# DRAM_BANK1.net
KiCad netlist of a schematic drawn in Altium Designer
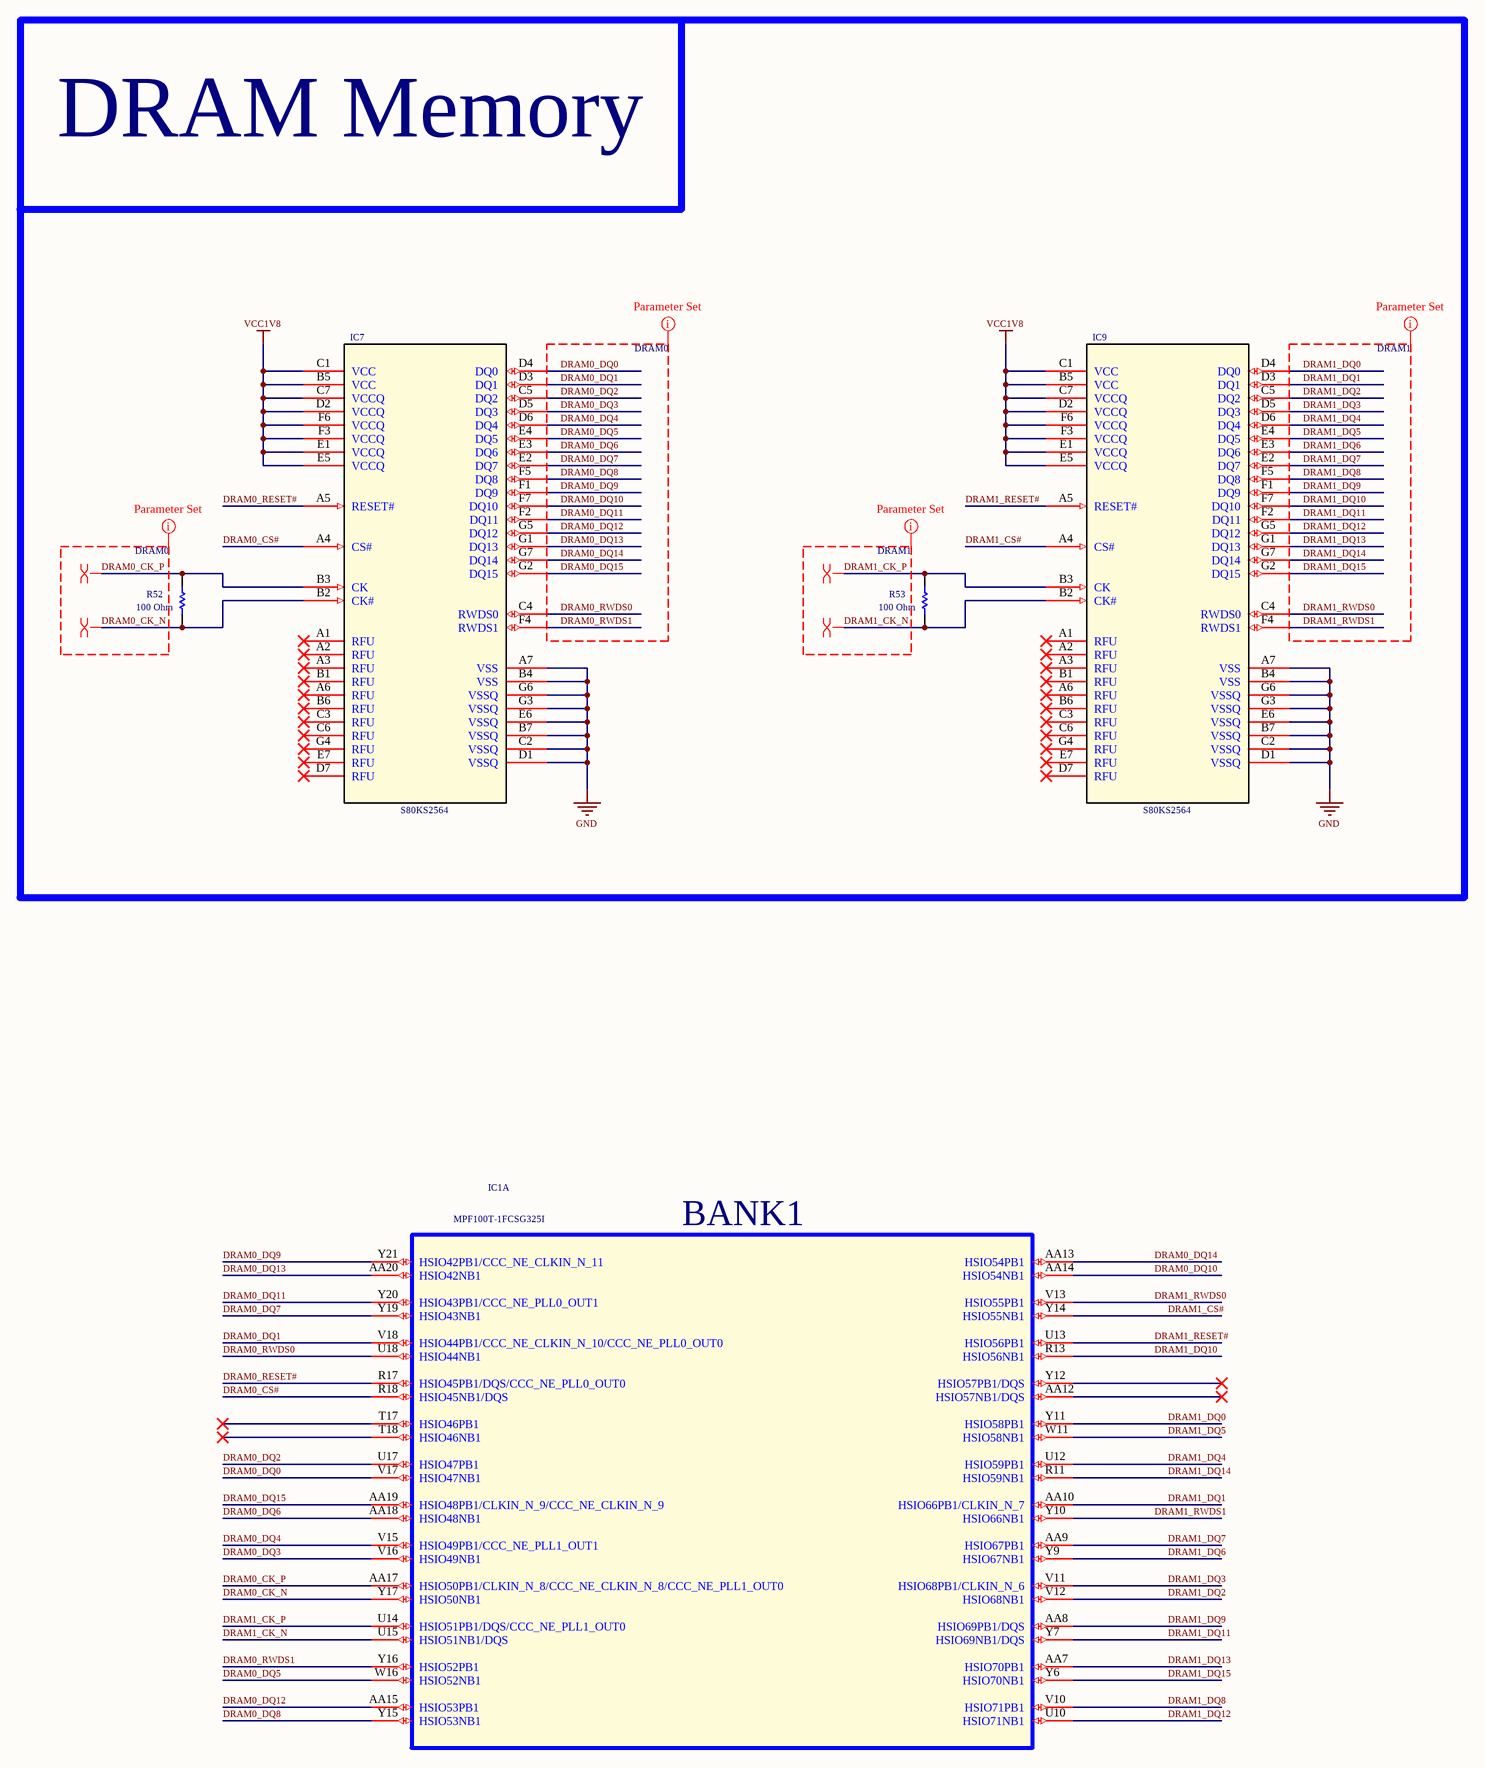
[diagram p0: DRAM+BANK1.SchDoc]

(export (version "E")
  (design (tool "Eeschema 10.0.6"))
  (components
    (comp (ref "IC1")
      (value "MPF100T-1FCSG325I")
      (footprint "PCB_Display_Doru:MPF100T-1FCSG325I")
      (fields (field (name "PART_NUMBER") "J00001"))
      (libsource (lib "PCB_Display_Doru") (part "MPF100T-1FCSG325I"))
    )
    (comp (ref "IC7")
      (value "S80KS2564")
      (footprint "PCB_Display_Doru:S80KS2564")
      (description "Jumper")
      (fields (field (name "PART_NUMBER") "J00001"))
      (libsource (lib "PCB_Display_Doru") (part "S80KS2564"))
    )
    (comp (ref "IC9")
      (value "S80KS2564")
      (footprint "PCB_Display_Doru:S80KS2564")
      (description "Jumper")
      (fields (field (name "PART_NUMBER") "J00001"))
      (libsource (lib "PCB_Display_Doru") (part "S80KS2564"))
    )
    (comp (ref "R52")
      (value "100 Ohm")
      (footprint "RESC1608X55X30LL15T15")
      (fields
        (field (name "MANUFACTURER") "Panasonic")
        (field (name "PART NUMBER") "ERJ-3EKF1000V")
        (field (name "MANUFACTURER PART NUMBER") "ERJ3EKF1000V")
      )
      (libsource (lib "PCB_Display_Doru") (part "CMP-2000-00179-1"))
    )
    (comp (ref "R53")
      (value "100 Ohm")
      (footprint "RESC1608X55X30LL15T15")
      (fields
        (field (name "MANUFACTURER") "Panasonic")
        (field (name "PART NUMBER") "ERJ-3EKF1000V")
        (field (name "MANUFACTURER PART NUMBER") "ERJ3EKF1000V")
      )
      (libsource (lib "PCB_Display_Doru") (part "CMP-2000-00179-1"))
    )
  )
  (nets
    (net (code "1") (name "/DRAM0_CK_N") (class "Default")
      (node (ref "IC1") (pin "Y17") (pinfunction "HSIO50NB1_Y17") (pintype "bidirectional"))
      (node (ref "IC7") (pin "B2") (pinfunction "CK#_B2") (pintype "input"))
      (node (ref "R52") (pin "1") (pinfunction "1_1") (pintype "passive"))
    )
    (net (code "2") (name "/DRAM0_CK_P") (class "Default")
      (node (ref "IC1") (pin "AA17") (pinfunction "HSIO50PB1/CLKIN_N_8/CCC_NE_CLKIN_N_8/CCC_NE_PLL1_OUT0_AA17") (pintype "bidirectional"))
      (node (ref "IC7") (pin "B3") (pinfunction "CK_B3") (pintype "input"))
      (node (ref "R52") (pin "2") (pinfunction "2_2") (pintype "passive"))
    )
    (net (code "3") (name "/DRAM0_CS#") (class "Default")
      (node (ref "IC1") (pin "R18") (pinfunction "HSIO45NB1/DQS_R18") (pintype "bidirectional"))
      (node (ref "IC7") (pin "A4") (pinfunction "CS#_A4") (pintype "input"))
    )
    (net (code "4") (name "/DRAM0_DQ0") (class "Default")
      (node (ref "IC1") (pin "V17") (pinfunction "HSIO47NB1_V17") (pintype "bidirectional"))
      (node (ref "IC7") (pin "D4") (pinfunction "DQ0_D4") (pintype "bidirectional"))
    )
    (net (code "5") (name "/DRAM0_DQ1") (class "Default")
      (node (ref "IC1") (pin "V18") (pinfunction "HSIO44PB1/CCC_NE_CLKIN_N_10/CCC_NE_PLL0_OUT0_V18") (pintype "bidirectional"))
      (node (ref "IC7") (pin "D3") (pinfunction "DQ1_D3") (pintype "bidirectional"))
    )
    (net (code "6") (name "/DRAM0_DQ2") (class "Default")
      (node (ref "IC1") (pin "U17") (pinfunction "HSIO47PB1_U17") (pintype "bidirectional"))
      (node (ref "IC7") (pin "C5") (pinfunction "DQ2_C5") (pintype "bidirectional"))
    )
    (net (code "7") (name "/DRAM0_DQ3") (class "Default")
      (node (ref "IC1") (pin "V16") (pinfunction "HSIO49NB1_V16") (pintype "bidirectional"))
      (node (ref "IC7") (pin "D5") (pinfunction "DQ3_D5") (pintype "bidirectional"))
    )
    (net (code "8") (name "/DRAM0_DQ4") (class "Default")
      (node (ref "IC1") (pin "V15") (pinfunction "HSIO49PB1/CCC_NE_PLL1_OUT1_V15") (pintype "bidirectional"))
      (node (ref "IC7") (pin "D6") (pinfunction "DQ4_D6") (pintype "bidirectional"))
    )
    (net (code "9") (name "/DRAM0_DQ5") (class "Default")
      (node (ref "IC1") (pin "W16") (pinfunction "HSIO52NB1_W16") (pintype "bidirectional"))
      (node (ref "IC7") (pin "E4") (pinfunction "DQ5_E4") (pintype "bidirectional"))
    )
    (net (code "10") (name "/DRAM0_DQ6") (class "Default")
      (node (ref "IC1") (pin "AA18") (pinfunction "HSIO48NB1_AA18") (pintype "bidirectional"))
      (node (ref "IC7") (pin "E3") (pinfunction "DQ6_E3") (pintype "bidirectional"))
    )
    (net (code "11") (name "/DRAM0_DQ7") (class "Default")
      (node (ref "IC1") (pin "Y19") (pinfunction "HSIO43NB1_Y19") (pintype "bidirectional"))
      (node (ref "IC7") (pin "E2") (pinfunction "DQ7_E2") (pintype "bidirectional"))
    )
    (net (code "12") (name "/DRAM0_DQ8") (class "Default")
      (node (ref "IC1") (pin "Y15") (pinfunction "HSIO53NB1_Y15") (pintype "bidirectional"))
      (node (ref "IC7") (pin "F5") (pinfunction "DQ8_F5") (pintype "bidirectional"))
    )
    (net (code "13") (name "/DRAM0_DQ9") (class "Default")
      (node (ref "IC1") (pin "Y21") (pinfunction "HSIO42PB1/CCC_NE_CLKIN_N_11_Y21") (pintype "bidirectional"))
      (node (ref "IC7") (pin "F1") (pinfunction "DQ9_F1") (pintype "bidirectional"))
    )
    (net (code "14") (name "/DRAM0_DQ10") (class "Default")
      (node (ref "IC1") (pin "AA14") (pinfunction "HSIO54NB1_AA14") (pintype "bidirectional"))
      (node (ref "IC7") (pin "F7") (pinfunction "DQ10_F7") (pintype "bidirectional"))
    )
    (net (code "15") (name "/DRAM0_DQ11") (class "Default")
      (node (ref "IC1") (pin "Y20") (pinfunction "HSIO43PB1/CCC_NE_PLL0_OUT1_Y20") (pintype "bidirectional"))
      (node (ref "IC7") (pin "F2") (pinfunction "DQ11_F2") (pintype "bidirectional"))
    )
    (net (code "16") (name "/DRAM0_DQ12") (class "Default")
      (node (ref "IC1") (pin "AA15") (pinfunction "HSIO53PB1_AA15") (pintype "bidirectional"))
      (node (ref "IC7") (pin "G5") (pinfunction "DQ12_G5") (pintype "bidirectional"))
    )
    (net (code "17") (name "/DRAM0_DQ13") (class "Default")
      (node (ref "IC1") (pin "AA20") (pinfunction "HSIO42NB1_AA20") (pintype "bidirectional"))
      (node (ref "IC7") (pin "G1") (pinfunction "DQ13_G1") (pintype "bidirectional"))
    )
    (net (code "18") (name "/DRAM0_DQ14") (class "Default")
      (node (ref "IC1") (pin "AA13") (pinfunction "HSIO54PB1_AA13") (pintype "bidirectional"))
      (node (ref "IC7") (pin "G7") (pinfunction "DQ14_G7") (pintype "bidirectional"))
    )
    (net (code "19") (name "/DRAM0_DQ15") (class "Default")
      (node (ref "IC1") (pin "AA19") (pinfunction "HSIO48PB1/CLKIN_N_9/CCC_NE_CLKIN_N_9_AA19") (pintype "bidirectional"))
      (node (ref "IC7") (pin "G2") (pinfunction "DQ15_G2") (pintype "bidirectional"))
    )
    (net (code "20") (name "/DRAM0_RESET#") (class "Default")
      (node (ref "IC1") (pin "R17") (pinfunction "HSIO45PB1/DQS/CCC_NE_PLL0_OUT0_R17") (pintype "bidirectional"))
      (node (ref "IC7") (pin "A5") (pinfunction "RESET#_A5") (pintype "input"))
    )
    (net (code "21") (name "/DRAM0_RWDS0") (class "Default")
      (node (ref "IC1") (pin "U18") (pinfunction "HSIO44NB1_U18") (pintype "bidirectional"))
      (node (ref "IC7") (pin "C4") (pinfunction "RWDS0_C4") (pintype "bidirectional"))
    )
    (net (code "22") (name "/DRAM0_RWDS1") (class "Default")
      (node (ref "IC1") (pin "Y16") (pinfunction "HSIO52PB1_Y16") (pintype "bidirectional"))
      (node (ref "IC7") (pin "F4") (pinfunction "RWDS1_F4") (pintype "bidirectional"))
    )
    (net (code "23") (name "/DRAM1_CK_N") (class "Default")
      (node (ref "IC1") (pin "U15") (pinfunction "HSIO51NB1/DQS_U15") (pintype "bidirectional"))
      (node (ref "IC9") (pin "B2") (pinfunction "CK#_B2") (pintype "input"))
      (node (ref "R53") (pin "1") (pinfunction "1_1") (pintype "passive"))
    )
    (net (code "24") (name "/DRAM1_CK_P") (class "Default")
      (node (ref "IC1") (pin "U14") (pinfunction "HSIO51PB1/DQS/CCC_NE_PLL1_OUT0_U14") (pintype "bidirectional"))
      (node (ref "IC9") (pin "B3") (pinfunction "CK_B3") (pintype "input"))
      (node (ref "R53") (pin "2") (pinfunction "2_2") (pintype "passive"))
    )
    (net (code "25") (name "/DRAM1_CS#") (class "Default")
      (node (ref "IC1") (pin "Y14") (pinfunction "HSIO55NB1_Y14") (pintype "bidirectional"))
      (node (ref "IC9") (pin "A4") (pinfunction "CS#_A4") (pintype "input"))
    )
    (net (code "26") (name "/DRAM1_DQ0") (class "Default")
      (node (ref "IC1") (pin "Y11") (pinfunction "HSIO58PB1_Y11") (pintype "bidirectional"))
      (node (ref "IC9") (pin "D4") (pinfunction "DQ0_D4") (pintype "bidirectional"))
    )
    (net (code "27") (name "/DRAM1_DQ1") (class "Default")
      (node (ref "IC1") (pin "AA10") (pinfunction "HSIO66PB1/CLKIN_N_7_AA10") (pintype "bidirectional"))
      (node (ref "IC9") (pin "D3") (pinfunction "DQ1_D3") (pintype "bidirectional"))
    )
    (net (code "28") (name "/DRAM1_DQ2") (class "Default")
      (node (ref "IC1") (pin "V12") (pinfunction "HSIO68NB1_V12") (pintype "bidirectional"))
      (node (ref "IC9") (pin "C5") (pinfunction "DQ2_C5") (pintype "bidirectional"))
    )
    (net (code "29") (name "/DRAM1_DQ3") (class "Default")
      (node (ref "IC1") (pin "V11") (pinfunction "HSIO68PB1/CLKIN_N_6_V11") (pintype "bidirectional"))
      (node (ref "IC9") (pin "D5") (pinfunction "DQ3_D5") (pintype "bidirectional"))
    )
    (net (code "30") (name "/DRAM1_DQ4") (class "Default")
      (node (ref "IC1") (pin "U12") (pinfunction "HSIO59PB1_U12") (pintype "bidirectional"))
      (node (ref "IC9") (pin "D6") (pinfunction "DQ4_D6") (pintype "bidirectional"))
    )
    (net (code "31") (name "/DRAM1_DQ5") (class "Default")
      (node (ref "IC1") (pin "W11") (pinfunction "HSIO58NB1_W11") (pintype "bidirectional"))
      (node (ref "IC9") (pin "E4") (pinfunction "DQ5_E4") (pintype "bidirectional"))
    )
    (net (code "32") (name "/DRAM1_DQ6") (class "Default")
      (node (ref "IC1") (pin "Y9") (pinfunction "HSIO67NB1_Y9") (pintype "bidirectional"))
      (node (ref "IC9") (pin "E3") (pinfunction "DQ6_E3") (pintype "bidirectional"))
    )
    (net (code "33") (name "/DRAM1_DQ7") (class "Default")
      (node (ref "IC1") (pin "AA9") (pinfunction "HSIO67PB1_AA9") (pintype "bidirectional"))
      (node (ref "IC9") (pin "E2") (pinfunction "DQ7_E2") (pintype "bidirectional"))
    )
    (net (code "34") (name "/DRAM1_DQ8") (class "Default")
      (node (ref "IC1") (pin "V10") (pinfunction "HSIO71PB1_V10") (pintype "bidirectional"))
      (node (ref "IC9") (pin "F5") (pinfunction "DQ8_F5") (pintype "bidirectional"))
    )
    (net (code "35") (name "/DRAM1_DQ9") (class "Default")
      (node (ref "IC1") (pin "AA8") (pinfunction "HSIO69PB1/DQS_AA8") (pintype "bidirectional"))
      (node (ref "IC9") (pin "F1") (pinfunction "DQ9_F1") (pintype "bidirectional"))
    )
    (net (code "36") (name "/DRAM1_DQ10") (class "Default")
      (node (ref "IC1") (pin "R13") (pinfunction "HSIO56NB1_R13") (pintype "bidirectional"))
      (node (ref "IC9") (pin "F7") (pinfunction "DQ10_F7") (pintype "bidirectional"))
    )
    (net (code "37") (name "/DRAM1_DQ11") (class "Default")
      (node (ref "IC1") (pin "Y7") (pinfunction "HSIO69NB1/DQS_Y7") (pintype "bidirectional"))
      (node (ref "IC9") (pin "F2") (pinfunction "DQ11_F2") (pintype "bidirectional"))
    )
    (net (code "38") (name "/DRAM1_DQ12") (class "Default")
      (node (ref "IC1") (pin "U10") (pinfunction "HSIO71NB1_U10") (pintype "bidirectional"))
      (node (ref "IC9") (pin "G5") (pinfunction "DQ12_G5") (pintype "bidirectional"))
    )
    (net (code "39") (name "/DRAM1_DQ13") (class "Default")
      (node (ref "IC1") (pin "AA7") (pinfunction "HSIO70PB1_AA7") (pintype "bidirectional"))
      (node (ref "IC9") (pin "G1") (pinfunction "DQ13_G1") (pintype "bidirectional"))
    )
    (net (code "40") (name "/DRAM1_DQ14") (class "Default")
      (node (ref "IC1") (pin "R11") (pinfunction "HSIO59NB1_R11") (pintype "bidirectional"))
      (node (ref "IC9") (pin "G7") (pinfunction "DQ14_G7") (pintype "bidirectional"))
    )
    (net (code "41") (name "/DRAM1_DQ15") (class "Default")
      (node (ref "IC1") (pin "Y6") (pinfunction "HSIO70NB1_Y6") (pintype "bidirectional"))
      (node (ref "IC9") (pin "G2") (pinfunction "DQ15_G2") (pintype "bidirectional"))
    )
    (net (code "42") (name "/DRAM1_RESET#") (class "Default")
      (node (ref "IC1") (pin "U13") (pinfunction "HSIO56PB1_U13") (pintype "bidirectional"))
      (node (ref "IC9") (pin "A5") (pinfunction "RESET#_A5") (pintype "input"))
    )
    (net (code "43") (name "/DRAM1_RWDS0") (class "Default")
      (node (ref "IC1") (pin "V13") (pinfunction "HSIO55PB1_V13") (pintype "bidirectional"))
      (node (ref "IC9") (pin "C4") (pinfunction "RWDS0_C4") (pintype "bidirectional"))
    )
    (net (code "44") (name "/DRAM1_RWDS1") (class "Default")
      (node (ref "IC1") (pin "Y10") (pinfunction "HSIO66NB1_Y10") (pintype "bidirectional"))
      (node (ref "IC9") (pin "F4") (pinfunction "RWDS1_F4") (pintype "bidirectional"))
    )
    (net (code "45") (name "GND") (class "Default")
      (node (ref "IC7") (pin "A7") (pinfunction "VSS_A7") (pintype "power_in"))
      (node (ref "IC7") (pin "B4") (pinfunction "VSS_B4") (pintype "power_in"))
      (node (ref "IC7") (pin "B7") (pinfunction "VSSQ_B7") (pintype "power_in"))
      (node (ref "IC7") (pin "C2") (pinfunction "VSSQ_C2") (pintype "power_in"))
      (node (ref "IC7") (pin "D1") (pinfunction "VSSQ_D1") (pintype "power_in"))
      (node (ref "IC7") (pin "E6") (pinfunction "VSSQ_E6") (pintype "power_in"))
      (node (ref "IC7") (pin "G3") (pinfunction "VSSQ_G3") (pintype "power_in"))
      (node (ref "IC7") (pin "G6") (pinfunction "VSSQ_G6") (pintype "power_in"))
      (node (ref "IC9") (pin "A7") (pinfunction "VSS_A7") (pintype "power_in"))
      (node (ref "IC9") (pin "B4") (pinfunction "VSS_B4") (pintype "power_in"))
      (node (ref "IC9") (pin "B7") (pinfunction "VSSQ_B7") (pintype "power_in"))
      (node (ref "IC9") (pin "C2") (pinfunction "VSSQ_C2") (pintype "power_in"))
      (node (ref "IC9") (pin "D1") (pinfunction "VSSQ_D1") (pintype "power_in"))
      (node (ref "IC9") (pin "E6") (pinfunction "VSSQ_E6") (pintype "power_in"))
      (node (ref "IC9") (pin "G3") (pinfunction "VSSQ_G3") (pintype "power_in"))
      (node (ref "IC9") (pin "G6") (pinfunction "VSSQ_G6") (pintype "power_in"))
    )
    (net (code "46") (name "VCC1V8") (class "Default")
      (node (ref "IC7") (pin "B5") (pinfunction "VCC_B5") (pintype "power_in"))
      (node (ref "IC7") (pin "C1") (pinfunction "VCC_C1") (pintype "power_in"))
      (node (ref "IC7") (pin "C7") (pinfunction "VCCQ_C7") (pintype "power_in"))
      (node (ref "IC7") (pin "D2") (pinfunction "VCCQ_D2") (pintype "power_in"))
      (node (ref "IC7") (pin "E1") (pinfunction "VCCQ_E1") (pintype "power_in"))
      (node (ref "IC7") (pin "E5") (pinfunction "VCCQ_E5") (pintype "power_in"))
      (node (ref "IC7") (pin "F3") (pinfunction "VCCQ_F3") (pintype "power_in"))
      (node (ref "IC7") (pin "F6") (pinfunction "VCCQ_F6") (pintype "power_in"))
      (node (ref "IC9") (pin "B5") (pinfunction "VCC_B5") (pintype "power_in"))
      (node (ref "IC9") (pin "C1") (pinfunction "VCC_C1") (pintype "power_in"))
      (node (ref "IC9") (pin "C7") (pinfunction "VCCQ_C7") (pintype "power_in"))
      (node (ref "IC9") (pin "D2") (pinfunction "VCCQ_D2") (pintype "power_in"))
      (node (ref "IC9") (pin "E1") (pinfunction "VCCQ_E1") (pintype "power_in"))
      (node (ref "IC9") (pin "E5") (pinfunction "VCCQ_E5") (pintype "power_in"))
      (node (ref "IC9") (pin "F3") (pinfunction "VCCQ_F3") (pintype "power_in"))
      (node (ref "IC9") (pin "F6") (pinfunction "VCCQ_F6") (pintype "power_in"))
    )
    (net (code "47") (name "unconnected-(IC1A-HSIO46NB1-PadT18)") (class "Default")
      (node (ref "IC1") (pin "T18") (pinfunction "HSIO46NB1_T18") (pintype "bidirectional+no_connect"))
    )
    (net (code "48") (name "unconnected-(IC1A-HSIO46PB1-PadT17)") (class "Default")
      (node (ref "IC1") (pin "T17") (pinfunction "HSIO46PB1_T17") (pintype "bidirectional+no_connect"))
    )
    (net (code "49") (name "unconnected-(IC1A-HSIO57NB1{slash}DQS-PadAA12)") (class "Default")
      (node (ref "IC1") (pin "AA12") (pinfunction "HSIO57NB1/DQS_AA12") (pintype "bidirectional+no_connect"))
    )
    (net (code "50") (name "unconnected-(IC1A-HSIO57PB1{slash}DQS-PadY12)") (class "Default")
      (node (ref "IC1") (pin "Y12") (pinfunction "HSIO57PB1/DQS_Y12") (pintype "bidirectional+no_connect"))
    )
    (net (code "51") (name "unconnected-(IC7-RFU-PadA1)") (class "Default")
      (node (ref "IC7") (pin "A1") (pinfunction "RFU_A1") (pintype "passive+no_connect"))
    )
    (net (code "52") (name "unconnected-(IC7-RFU-PadA2)") (class "Default")
      (node (ref "IC7") (pin "A2") (pinfunction "RFU_A2") (pintype "passive+no_connect"))
    )
    (net (code "53") (name "unconnected-(IC7-RFU-PadA3)") (class "Default")
      (node (ref "IC7") (pin "A3") (pinfunction "RFU_A3") (pintype "passive+no_connect"))
    )
    (net (code "54") (name "unconnected-(IC7-RFU-PadA6)") (class "Default")
      (node (ref "IC7") (pin "A6") (pinfunction "RFU_A6") (pintype "passive+no_connect"))
    )
    (net (code "55") (name "unconnected-(IC7-RFU-PadB1)") (class "Default")
      (node (ref "IC7") (pin "B1") (pinfunction "RFU_B1") (pintype "passive+no_connect"))
    )
    (net (code "56") (name "unconnected-(IC7-RFU-PadB6)") (class "Default")
      (node (ref "IC7") (pin "B6") (pinfunction "RFU_B6") (pintype "passive+no_connect"))
    )
    (net (code "57") (name "unconnected-(IC7-RFU-PadC3)") (class "Default")
      (node (ref "IC7") (pin "C3") (pinfunction "RFU_C3") (pintype "passive+no_connect"))
    )
    (net (code "58") (name "unconnected-(IC7-RFU-PadC6)") (class "Default")
      (node (ref "IC7") (pin "C6") (pinfunction "RFU_C6") (pintype "passive+no_connect"))
    )
    (net (code "59") (name "unconnected-(IC7-RFU-PadD7)") (class "Default")
      (node (ref "IC7") (pin "D7") (pinfunction "RFU_D7") (pintype "passive+no_connect"))
    )
    (net (code "60") (name "unconnected-(IC7-RFU-PadE7)") (class "Default")
      (node (ref "IC7") (pin "E7") (pinfunction "RFU_E7") (pintype "passive+no_connect"))
    )
    (net (code "61") (name "unconnected-(IC7-RFU-PadG4)") (class "Default")
      (node (ref "IC7") (pin "G4") (pinfunction "RFU_G4") (pintype "passive+no_connect"))
    )
    (net (code "62") (name "unconnected-(IC9-RFU-PadA1)") (class "Default")
      (node (ref "IC9") (pin "A1") (pinfunction "RFU_A1") (pintype "passive+no_connect"))
    )
    (net (code "63") (name "unconnected-(IC9-RFU-PadA2)") (class "Default")
      (node (ref "IC9") (pin "A2") (pinfunction "RFU_A2") (pintype "passive+no_connect"))
    )
    (net (code "64") (name "unconnected-(IC9-RFU-PadA3)") (class "Default")
      (node (ref "IC9") (pin "A3") (pinfunction "RFU_A3") (pintype "passive+no_connect"))
    )
    (net (code "65") (name "unconnected-(IC9-RFU-PadA6)") (class "Default")
      (node (ref "IC9") (pin "A6") (pinfunction "RFU_A6") (pintype "passive+no_connect"))
    )
    (net (code "66") (name "unconnected-(IC9-RFU-PadB1)") (class "Default")
      (node (ref "IC9") (pin "B1") (pinfunction "RFU_B1") (pintype "passive+no_connect"))
    )
    (net (code "67") (name "unconnected-(IC9-RFU-PadB6)") (class "Default")
      (node (ref "IC9") (pin "B6") (pinfunction "RFU_B6") (pintype "passive+no_connect"))
    )
    (net (code "68") (name "unconnected-(IC9-RFU-PadC3)") (class "Default")
      (node (ref "IC9") (pin "C3") (pinfunction "RFU_C3") (pintype "passive+no_connect"))
    )
    (net (code "69") (name "unconnected-(IC9-RFU-PadC6)") (class "Default")
      (node (ref "IC9") (pin "C6") (pinfunction "RFU_C6") (pintype "passive+no_connect"))
    )
    (net (code "70") (name "unconnected-(IC9-RFU-PadD7)") (class "Default")
      (node (ref "IC9") (pin "D7") (pinfunction "RFU_D7") (pintype "passive+no_connect"))
    )
    (net (code "71") (name "unconnected-(IC9-RFU-PadE7)") (class "Default")
      (node (ref "IC9") (pin "E7") (pinfunction "RFU_E7") (pintype "passive+no_connect"))
    )
    (net (code "72") (name "unconnected-(IC9-RFU-PadG4)") (class "Default")
      (node (ref "IC9") (pin "G4") (pinfunction "RFU_G4") (pintype "passive+no_connect"))
    )
  )
)
